# Group_05.net
KiCad netlist of a schematic drawn in EAGLE
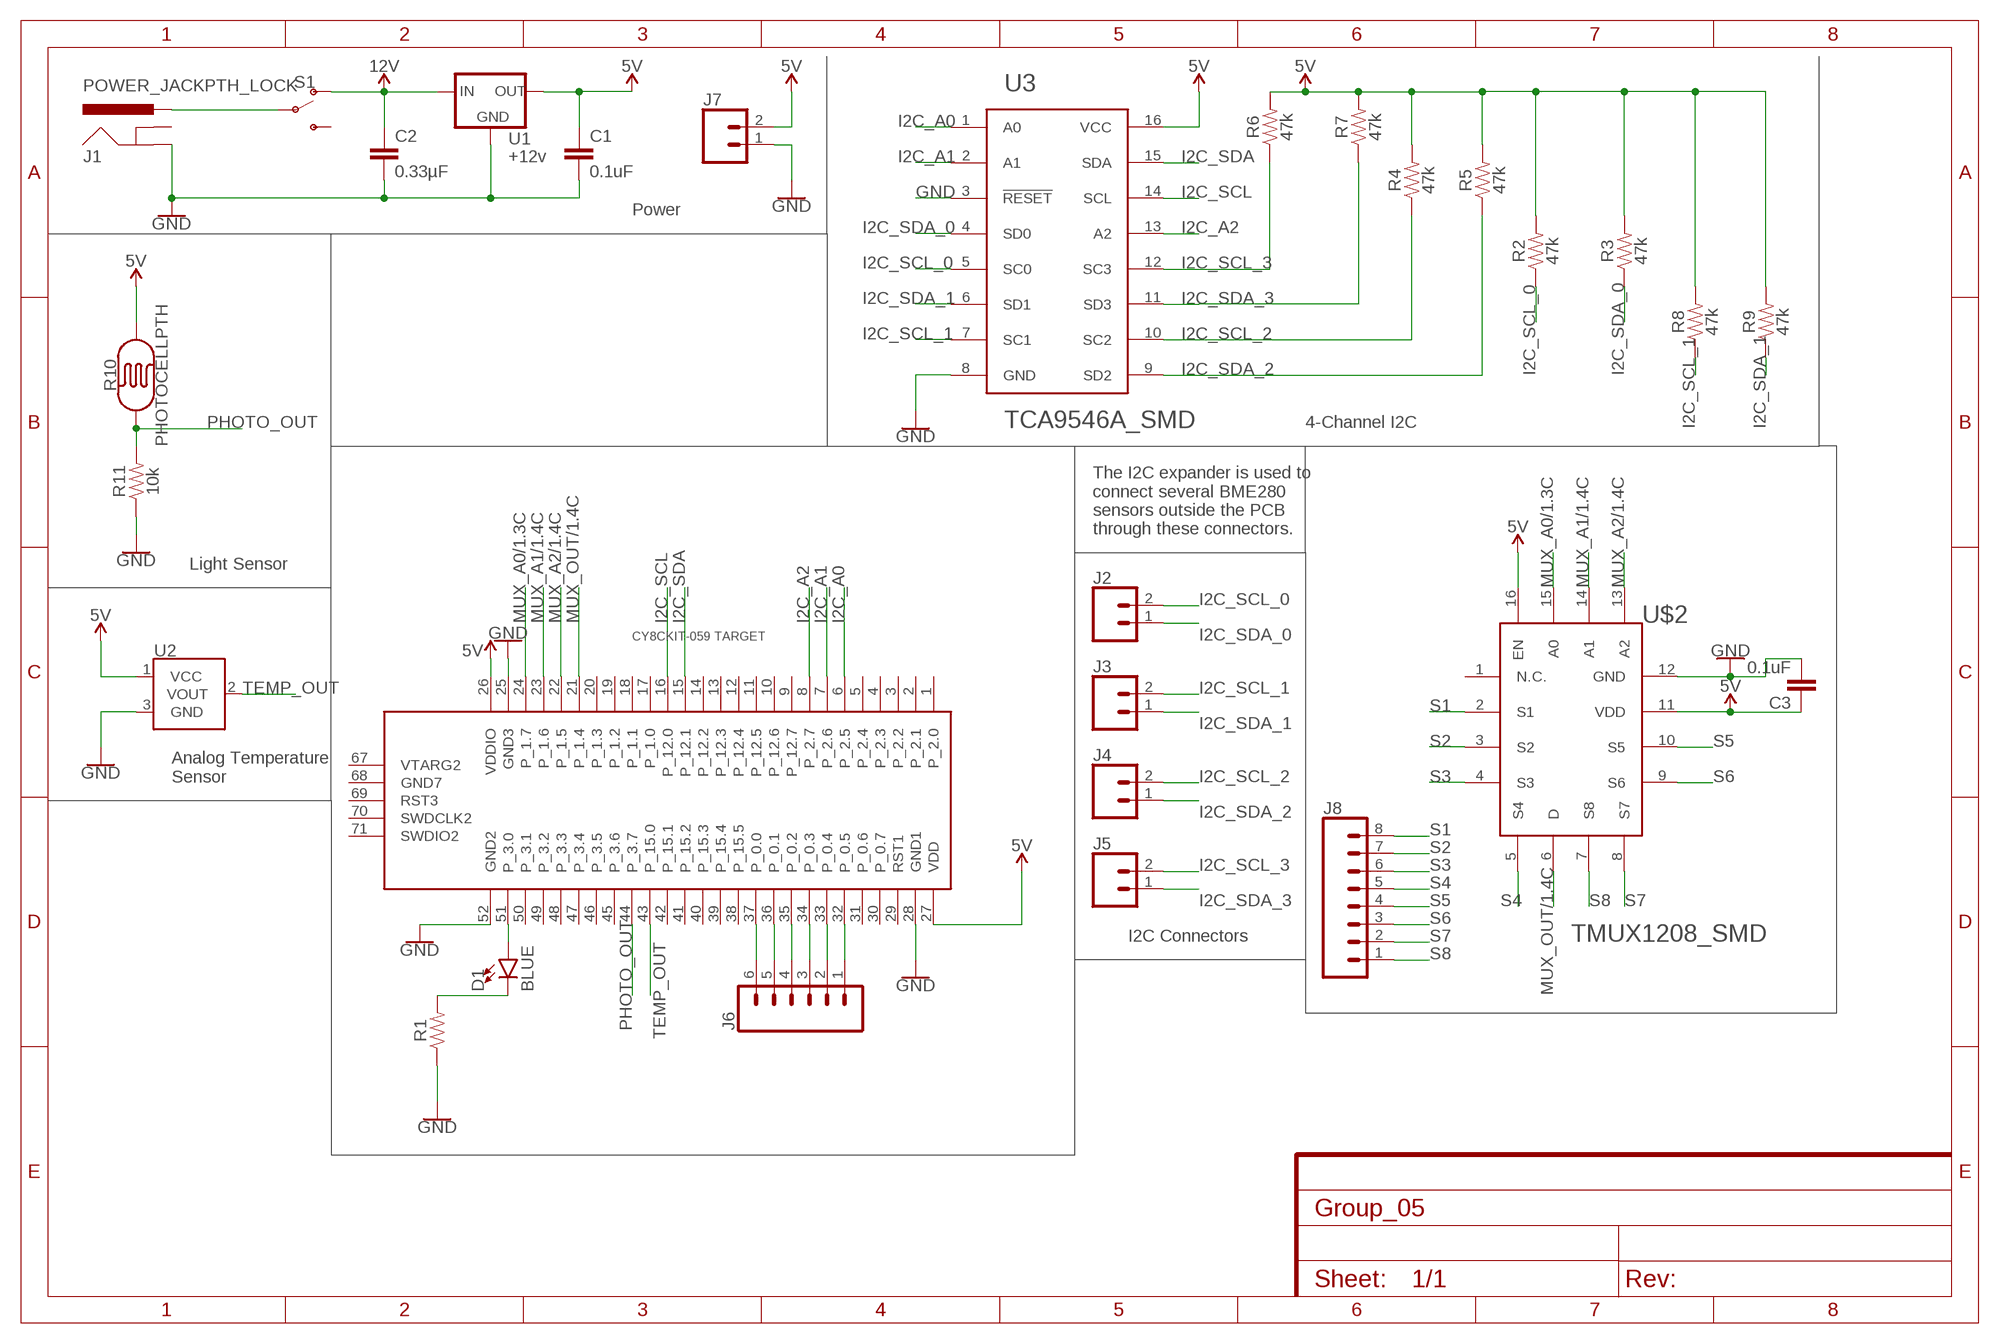
[diagram p0: schematic, sheet 1]

(export (version "E")
  (design (tool "Eeschema 10.0.6"))
  (components
    (comp (ref "C1")
      (value "0.1uF")
      (footprint "eagle-import:CAP-PTH-SMALL-KIT")
      (libsource (lib "eagle-import") (part "0.1UF-KIT-EZ-50V-20%"))
    )
    (comp (ref "C2")
      (value "0.33µF")
      (footprint "eagle-import:0805")
      (libsource (lib "eagle-import") (part "0.33UF/330NF-0805-50V-10%"))
    )
    (comp (ref "C3")
      (value "0.1uF")
      (footprint "eagle-import:CAP-PTH-SMALL-KIT")
      (libsource (lib "eagle-import") (part "0.1UF-KIT-EZ-50V-20%"))
    )
    (comp (ref "D1")
      (value "BLUE")
      (footprint "eagle-import:LED-1206")
      (libsource (lib "eagle-import") (part "LED-BLUE1206"))
    )
    (comp (ref "J1")
      (value "POWER_JACKPTH_LOCK")
      (footprint "eagle-import:POWER_JACK_PTH_LOCK")
      (libsource (lib "eagle-import") (part "POWER_JACKPTH_LOCK"))
    )
    (comp (ref "J2")
      (value "CONN_02")
      (footprint "eagle-import:1X02")
      (libsource (lib "eagle-import") (part "CONN_02"))
    )
    (comp (ref "J3")
      (value "CONN_02")
      (footprint "eagle-import:1X02")
      (libsource (lib "eagle-import") (part "CONN_02"))
    )
    (comp (ref "J4")
      (value "CONN_02")
      (footprint "eagle-import:1X02")
      (libsource (lib "eagle-import") (part "CONN_02"))
    )
    (comp (ref "J5")
      (value "CONN_02")
      (footprint "eagle-import:1X02")
      (libsource (lib "eagle-import") (part "CONN_02"))
    )
    (comp (ref "J6")
      (value "CONN_06LOCK")
      (footprint "eagle-import:1X06_LOCK")
      (libsource (lib "eagle-import") (part "CONN_06LOCK"))
    )
    (comp (ref "J7")
      (value "CONN_02")
      (footprint "eagle-import:1X02")
      (libsource (lib "eagle-import") (part "CONN_02"))
    )
    (comp (ref "J8")
      (value "CONN_08LOCK")
      (footprint "eagle-import:1X08_LOCK")
      (libsource (lib "eagle-import") (part "CONN_08LOCK"))
    )
    (comp (ref "R1")
      (value "RESISTORAXIAL-0.3")
      (footprint "eagle-import:AXIAL-0.3")
      (libsource (lib "eagle-import") (part "RESISTORAXIAL-0.3"))
    )
    (comp (ref "R2")
      (value "47k")
      (footprint "eagle-import:0603")
      (libsource (lib "eagle-import") (part "47KOHM-0603-1/10W-1%"))
    )
    (comp (ref "R3")
      (value "47k")
      (footprint "eagle-import:0603")
      (libsource (lib "eagle-import") (part "47KOHM-0603-1/10W-1%"))
    )
    (comp (ref "R4")
      (value "47k")
      (footprint "eagle-import:0603")
      (libsource (lib "eagle-import") (part "47KOHM-0603-1/10W-1%"))
    )
    (comp (ref "R5")
      (value "47k")
      (footprint "eagle-import:0603")
      (libsource (lib "eagle-import") (part "47KOHM-0603-1/10W-1%"))
    )
    (comp (ref "R6")
      (value "47k")
      (footprint "eagle-import:0603")
      (libsource (lib "eagle-import") (part "47KOHM-0603-1/10W-1%"))
    )
    (comp (ref "R7")
      (value "47k")
      (footprint "eagle-import:0603")
      (libsource (lib "eagle-import") (part "47KOHM-0603-1/10W-1%"))
    )
    (comp (ref "R8")
      (value "47k")
      (footprint "eagle-import:0603")
      (libsource (lib "eagle-import") (part "47KOHM-0603-1/10W-1%"))
    )
    (comp (ref "R9")
      (value "47k")
      (footprint "eagle-import:0603")
      (libsource (lib "eagle-import") (part "47KOHM-0603-1/10W-1%"))
    )
    (comp (ref "R10")
      (value "PHOTOCELLPTH")
      (footprint "eagle-import:PHOTOCELL")
      (libsource (lib "eagle-import") (part "PHOTOCELLPTH"))
    )
    (comp (ref "R11")
      (value "10k")
      (footprint "eagle-import:0603")
      (libsource (lib "eagle-import") (part "10KOHM-0603-1/10W-1%"))
    )
    (comp (ref "S1")
      (value "SWITCH-SPDT-PTH-11.6X4.0MM")
      (footprint "eagle-import:SWITCH_SPDT_PTH_11.6X4.0MM")
      (libsource (lib "eagle-import") (part "SWITCH-SPDT-PTH-11.6X4.0MM"))
    )
    (comp (ref "U$1")
      (value "CY8CKIT-059_TARGET")
      (footprint "eagle-import:CY8CKIT-059_TARGET")
      (libsource (lib "eagle-import") (part "CY8CKIT-059_TARGET"))
    )
    (comp (ref "U$2")
      (value "TMUX1208_SMD")
      (footprint "eagle-import:QFN16")
      (libsource (lib "eagle-import") (part "TMUX1208_SMD"))
    )
    (comp (ref "U1")
      (value "+12v")
      (footprint "eagle-import:TO-252")
      (libsource (lib "eagle-import") (part "V_REG_78XX7812"))
    )
    (comp (ref "U2")
      (value "TMP36GT9")
      (footprint "eagle-import:TO-92")
      (libsource (lib "eagle-import") (part "TMP36GT9"))
    )
    (comp (ref "U3")
      (value "TCA9546A_SMD")
      (footprint "eagle-import:TSSOP16")
      (libsource (lib "eagle-import") (part "TCA9546A_SMD"))
    )
  )
  (nets
    (net (code "1") (name "/I2C_A0") (class "Default")
      (node (ref "U$1") (pin "6") (pinfunction "P_2.5_6") (pintype "bidirectional"))
      (node (ref "U3") (pin "1") (pinfunction "A0_1") (pintype "bidirectional"))
    )
    (net (code "2") (name "/I2C_A1") (class "Default")
      (node (ref "U$1") (pin "7") (pinfunction "P_2.6_7") (pintype "bidirectional"))
      (node (ref "U3") (pin "2") (pinfunction "A1_2") (pintype "bidirectional"))
    )
    (net (code "3") (name "/I2C_A2") (class "Default")
      (node (ref "U$1") (pin "8") (pinfunction "P_2.7_8") (pintype "bidirectional"))
      (node (ref "U3") (pin "13") (pinfunction "A2_13") (pintype "bidirectional"))
    )
    (net (code "4") (name "/I2C_SCL") (class "Default")
      (node (ref "U$1") (pin "16") (pinfunction "P_12.0_16") (pintype "bidirectional"))
      (node (ref "U3") (pin "14") (pinfunction "SCL_14") (pintype "bidirectional"))
    )
    (net (code "5") (name "/I2C_SCL_0") (class "Default")
      (node (ref "J2") (pin "2") (pinfunction "2_2") (pintype "passive"))
      (node (ref "R2") (pin "1") (pinfunction "1_1") (pintype "passive"))
      (node (ref "U3") (pin "5") (pinfunction "SC0_5") (pintype "bidirectional"))
    )
    (net (code "6") (name "/I2C_SCL_1") (class "Default")
      (node (ref "J3") (pin "2") (pinfunction "2_2") (pintype "passive"))
      (node (ref "R8") (pin "1") (pinfunction "1_1") (pintype "passive"))
      (node (ref "U3") (pin "7") (pinfunction "SC1_7") (pintype "bidirectional"))
    )
    (net (code "7") (name "/I2C_SCL_2") (class "Default")
      (node (ref "J4") (pin "2") (pinfunction "2_2") (pintype "passive"))
      (node (ref "R4") (pin "1") (pinfunction "1_1") (pintype "passive"))
      (node (ref "U3") (pin "10") (pinfunction "SC2_10") (pintype "bidirectional"))
    )
    (net (code "8") (name "/I2C_SCL_3") (class "Default")
      (node (ref "J5") (pin "2") (pinfunction "2_2") (pintype "passive"))
      (node (ref "R6") (pin "1") (pinfunction "1_1") (pintype "passive"))
      (node (ref "U3") (pin "12") (pinfunction "SC3_12") (pintype "bidirectional"))
    )
    (net (code "9") (name "/I2C_SDA") (class "Default")
      (node (ref "U$1") (pin "15") (pinfunction "P_12.1_15") (pintype "bidirectional"))
      (node (ref "U3") (pin "15") (pinfunction "SDA_15") (pintype "bidirectional"))
    )
    (net (code "10") (name "/I2C_SDA_0") (class "Default")
      (node (ref "J2") (pin "1") (pinfunction "1_1") (pintype "passive"))
      (node (ref "R3") (pin "1") (pinfunction "1_1") (pintype "passive"))
      (node (ref "U3") (pin "4") (pinfunction "SD0_4") (pintype "bidirectional"))
    )
    (net (code "11") (name "/I2C_SDA_1") (class "Default")
      (node (ref "J3") (pin "1") (pinfunction "1_1") (pintype "passive"))
      (node (ref "R9") (pin "1") (pinfunction "1_1") (pintype "passive"))
      (node (ref "U3") (pin "6") (pinfunction "SD1_6") (pintype "bidirectional"))
    )
    (net (code "12") (name "/I2C_SDA_2") (class "Default")
      (node (ref "J4") (pin "1") (pinfunction "1_1") (pintype "passive"))
      (node (ref "R5") (pin "1") (pinfunction "1_1") (pintype "passive"))
      (node (ref "U3") (pin "9") (pinfunction "SD2_9") (pintype "bidirectional"))
    )
    (net (code "13") (name "/I2C_SDA_3") (class "Default")
      (node (ref "J5") (pin "1") (pinfunction "1_1") (pintype "passive"))
      (node (ref "R7") (pin "1") (pinfunction "1_1") (pintype "passive"))
      (node (ref "U3") (pin "11") (pinfunction "SD3_11") (pintype "bidirectional"))
    )
    (net (code "14") (name "/MUX_A0{slash}1.3C") (class "Default")
      (node (ref "U$1") (pin "24") (pinfunction "P_1.7_24") (pintype "bidirectional"))
      (node (ref "U$2") (pin "15") (pinfunction "A0_15") (pintype "bidirectional"))
    )
    (net (code "15") (name "/MUX_A1{slash}1.4C") (class "Default")
      (node (ref "U$1") (pin "23") (pinfunction "P_1.6_23") (pintype "bidirectional"))
      (node (ref "U$2") (pin "14") (pinfunction "A1_14") (pintype "bidirectional"))
    )
    (net (code "16") (name "/MUX_A2{slash}1.4C") (class "Default")
      (node (ref "U$1") (pin "22") (pinfunction "P_1.5_22") (pintype "bidirectional"))
      (node (ref "U$2") (pin "13") (pinfunction "A2_13") (pintype "bidirectional"))
    )
    (net (code "17") (name "/MUX_OUT{slash}1.4C") (class "Default")
      (node (ref "U$1") (pin "21") (pinfunction "P_1.4_21") (pintype "bidirectional"))
      (node (ref "U$2") (pin "6") (pinfunction "D_6") (pintype "bidirectional"))
    )
    (net (code "18") (name "/PHOTO_OUT") (class "Default")
      (node (ref "R10") (pin "1") (pinfunction "P$1_1") (pintype "bidirectional"))
      (node (ref "R11") (pin "2") (pinfunction "2_2") (pintype "passive"))
      (node (ref "U$1") (pin "44") (pinfunction "P_3.7_44") (pintype "bidirectional"))
    )
    (net (code "19") (name "/S1") (class "Default")
      (node (ref "J8") (pin "8") (pinfunction "8_8") (pintype "passive"))
      (node (ref "U$2") (pin "2") (pinfunction "S1_2") (pintype "bidirectional"))
    )
    (net (code "20") (name "/S2") (class "Default")
      (node (ref "J8") (pin "7") (pinfunction "7_7") (pintype "passive"))
      (node (ref "U$2") (pin "3") (pinfunction "S2_3") (pintype "bidirectional"))
    )
    (net (code "21") (name "/S3") (class "Default")
      (node (ref "J8") (pin "6") (pinfunction "6_6") (pintype "passive"))
      (node (ref "U$2") (pin "4") (pinfunction "S3_4") (pintype "bidirectional"))
    )
    (net (code "22") (name "/S4") (class "Default")
      (node (ref "J8") (pin "5") (pinfunction "5_5") (pintype "passive"))
      (node (ref "U$2") (pin "5") (pinfunction "S4_5") (pintype "bidirectional"))
    )
    (net (code "23") (name "/S5") (class "Default")
      (node (ref "J8") (pin "4") (pinfunction "4_4") (pintype "passive"))
      (node (ref "U$2") (pin "10") (pinfunction "S5_10") (pintype "bidirectional"))
    )
    (net (code "24") (name "/S6") (class "Default")
      (node (ref "J8") (pin "3") (pinfunction "3_3") (pintype "passive"))
      (node (ref "U$2") (pin "9") (pinfunction "S6_9") (pintype "bidirectional"))
    )
    (net (code "25") (name "/S7") (class "Default")
      (node (ref "J8") (pin "2") (pinfunction "2_2") (pintype "passive"))
      (node (ref "U$2") (pin "8") (pinfunction "S7_8") (pintype "bidirectional"))
    )
    (net (code "26") (name "/S8") (class "Default")
      (node (ref "J8") (pin "1") (pinfunction "1_1") (pintype "passive"))
      (node (ref "U$2") (pin "7") (pinfunction "S8_7") (pintype "bidirectional"))
    )
    (net (code "27") (name "/TEMP_OUT") (class "Default")
      (node (ref "U$1") (pin "43") (pinfunction "P_15.0_43") (pintype "bidirectional"))
      (node (ref "U2") (pin "2") (pinfunction "VOUT_2") (pintype "bidirectional"))
    )
    (net (code "28") (name "5V") (class "Default")
      (node (ref "C1") (pin "1") (pinfunction "1_1") (pintype "passive"))
      (node (ref "C3") (pin "1") (pinfunction "1_1") (pintype "passive"))
      (node (ref "J7") (pin "2") (pinfunction "2_2") (pintype "passive"))
      (node (ref "R10") (pin "2") (pinfunction "P$2_2") (pintype "bidirectional"))
      (node (ref "R2") (pin "2") (pinfunction "2_2") (pintype "passive"))
      (node (ref "R3") (pin "2") (pinfunction "2_2") (pintype "passive"))
      (node (ref "R4") (pin "2") (pinfunction "2_2") (pintype "passive"))
      (node (ref "R5") (pin "2") (pinfunction "2_2") (pintype "passive"))
      (node (ref "R6") (pin "2") (pinfunction "2_2") (pintype "passive"))
      (node (ref "R7") (pin "2") (pinfunction "2_2") (pintype "passive"))
      (node (ref "R8") (pin "2") (pinfunction "2_2") (pintype "passive"))
      (node (ref "R9") (pin "2") (pinfunction "2_2") (pintype "passive"))
      (node (ref "U$1") (pin "26") (pinfunction "VDDIO_26") (pintype "bidirectional"))
      (node (ref "U$1") (pin "27") (pinfunction "VDD_27") (pintype "bidirectional"))
      (node (ref "U$2") (pin "11") (pinfunction "VDD_11") (pintype "bidirectional"))
      (node (ref "U$2") (pin "16") (pinfunction "EN_16") (pintype "bidirectional"))
      (node (ref "U1") (pin "2") (pinfunction "OUT_2") (pintype "passive"))
      (node (ref "U2") (pin "1") (pinfunction "VCC_1") (pintype "bidirectional"))
      (node (ref "U3") (pin "16") (pinfunction "VCC_16") (pintype "bidirectional"))
    )
    (net (code "29") (name "12V") (class "Default")
      (node (ref "C2") (pin "1") (pinfunction "1_1") (pintype "passive"))
      (node (ref "S1") (pin "1") (pinfunction "O_1") (pintype "passive"))
      (node (ref "U1") (pin "1") (pinfunction "IN_1") (pintype "input"))
    )
    (net (code "30") (name "GND") (class "Default")
      (node (ref "C1") (pin "2") (pinfunction "2_2") (pintype "passive"))
      (node (ref "C2") (pin "2") (pinfunction "2_2") (pintype "passive"))
      (node (ref "C3") (pin "2") (pinfunction "2_2") (pintype "passive"))
      (node (ref "J1") (pin "GND") (pinfunction "GND_GND") (pintype "bidirectional"))
      (node (ref "J7") (pin "1") (pinfunction "1_1") (pintype "passive"))
      (node (ref "R1") (pin "P$1") (pinfunction "1_P$1") (pintype "passive"))
      (node (ref "R11") (pin "1") (pinfunction "1_1") (pintype "passive"))
      (node (ref "U$1") (pin "25") (pinfunction "GND3_25") (pintype "bidirectional"))
      (node (ref "U$1") (pin "28") (pinfunction "GND1_28") (pintype "bidirectional"))
      (node (ref "U$1") (pin "52") (pinfunction "GND2_52") (pintype "bidirectional"))
      (node (ref "U$2") (pin "12") (pinfunction "GND_12") (pintype "bidirectional"))
      (node (ref "U1") (pin "3") (pinfunction "GND_3") (pintype "input"))
      (node (ref "U2") (pin "3") (pinfunction "GND_3") (pintype "bidirectional"))
      (node (ref "U3") (pin "3") (pinfunction "~{RESET}_3") (pintype "bidirectional"))
      (node (ref "U3") (pin "8") (pinfunction "GND_8") (pintype "bidirectional"))
    )
    (net (code "31") (name "Net-(R1-2)") (class "Default")
      (node (ref "D1") (pin "C") (pinfunction "C_C") (pintype "passive"))
      (node (ref "R1") (pin "P$2") (pinfunction "2_P$2") (pintype "passive"))
    )
    (net (code "32") (name "Net-(S1-P)") (class "Default")
      (node (ref "J1") (pin "PWR") (pinfunction "PWR_PWR") (pintype "bidirectional"))
      (node (ref "S1") (pin "2") (pinfunction "P_2") (pintype "passive"))
    )
    (net (code "33") (name "Net-(U$1-P_0.0)") (class "Default")
      (node (ref "J6") (pin "6") (pinfunction "6_6") (pintype "passive"))
      (node (ref "U$1") (pin "37") (pinfunction "P_0.0_37") (pintype "bidirectional"))
    )
    (net (code "34") (name "Net-(U$1-P_0.1)") (class "Default")
      (node (ref "J6") (pin "5") (pinfunction "5_5") (pintype "passive"))
      (node (ref "U$1") (pin "36") (pinfunction "P_0.1_36") (pintype "bidirectional"))
    )
    (net (code "35") (name "Net-(U$1-P_0.2)") (class "Default")
      (node (ref "J6") (pin "4") (pinfunction "4_4") (pintype "passive"))
      (node (ref "U$1") (pin "35") (pinfunction "P_0.2_35") (pintype "bidirectional"))
    )
    (net (code "36") (name "Net-(U$1-P_0.3)") (class "Default")
      (node (ref "J6") (pin "3") (pinfunction "3_3") (pintype "passive"))
      (node (ref "U$1") (pin "34") (pinfunction "P_0.3_34") (pintype "bidirectional"))
    )
    (net (code "37") (name "Net-(U$1-P_0.4)") (class "Default")
      (node (ref "J6") (pin "2") (pinfunction "2_2") (pintype "passive"))
      (node (ref "U$1") (pin "33") (pinfunction "P_0.4_33") (pintype "bidirectional"))
    )
    (net (code "38") (name "Net-(U$1-P_0.5)") (class "Default")
      (node (ref "J6") (pin "1") (pinfunction "1_1") (pintype "passive"))
      (node (ref "U$1") (pin "32") (pinfunction "P_0.5_32") (pintype "bidirectional"))
    )
    (net (code "39") (name "Net-(U$1-P_3.0)") (class "Default")
      (node (ref "D1") (pin "A") (pinfunction "A_A") (pintype "passive"))
      (node (ref "U$1") (pin "51") (pinfunction "P_3.0_51") (pintype "bidirectional"))
    )
    (net (code "40") (name "unconnected-(J1-PadGNDBREAK)") (class "Default")
      (node (ref "J1") (pin "GNDBREAK") (pinfunction "GNDBREAK_GNDBREAK") (pintype "bidirectional"))
    )
    (net (code "41") (name "unconnected-(S1-S-Pad3)") (class "Default")
      (node (ref "S1") (pin "3") (pinfunction "S_3") (pintype "passive"))
    )
    (net (code "42") (name "unconnected-(U$1-GND7-Pad68)") (class "Default")
      (node (ref "U$1") (pin "68") (pinfunction "GND7_68") (pintype "bidirectional"))
    )
    (net (code "43") (name "unconnected-(U$1-P_0.6-Pad31)") (class "Default")
      (node (ref "U$1") (pin "31") (pinfunction "P_0.6_31") (pintype "bidirectional"))
    )
    (net (code "44") (name "unconnected-(U$1-P_0.7-Pad30)") (class "Default")
      (node (ref "U$1") (pin "30") (pinfunction "P_0.7_30") (pintype "bidirectional"))
    )
    (net (code "45") (name "unconnected-(U$1-P_1.0-Pad17)") (class "Default")
      (node (ref "U$1") (pin "17") (pinfunction "P_1.0_17") (pintype "bidirectional"))
    )
    (net (code "46") (name "unconnected-(U$1-P_1.1-Pad18)") (class "Default")
      (node (ref "U$1") (pin "18") (pinfunction "P_1.1_18") (pintype "bidirectional"))
    )
    (net (code "47") (name "unconnected-(U$1-P_1.2-Pad19)") (class "Default")
      (node (ref "U$1") (pin "19") (pinfunction "P_1.2_19") (pintype "bidirectional"))
    )
    (net (code "48") (name "unconnected-(U$1-P_1.3-Pad20)") (class "Default")
      (node (ref "U$1") (pin "20") (pinfunction "P_1.3_20") (pintype "bidirectional"))
    )
    (net (code "49") (name "unconnected-(U$1-P_2.0-Pad1)") (class "Default")
      (node (ref "U$1") (pin "1") (pinfunction "P_2.0_1") (pintype "bidirectional"))
    )
    (net (code "50") (name "unconnected-(U$1-P_2.1-Pad2)") (class "Default")
      (node (ref "U$1") (pin "2") (pinfunction "P_2.1_2") (pintype "bidirectional"))
    )
    (net (code "51") (name "unconnected-(U$1-P_2.2-Pad3)") (class "Default")
      (node (ref "U$1") (pin "3") (pinfunction "P_2.2_3") (pintype "bidirectional"))
    )
    (net (code "52") (name "unconnected-(U$1-P_2.3-Pad4)") (class "Default")
      (node (ref "U$1") (pin "4") (pinfunction "P_2.3_4") (pintype "bidirectional"))
    )
    (net (code "53") (name "unconnected-(U$1-P_2.4-Pad5)") (class "Default")
      (node (ref "U$1") (pin "5") (pinfunction "P_2.4_5") (pintype "bidirectional"))
    )
    (net (code "54") (name "unconnected-(U$1-P_3.1-Pad50)") (class "Default")
      (node (ref "U$1") (pin "50") (pinfunction "P_3.1_50") (pintype "bidirectional"))
    )
    (net (code "55") (name "unconnected-(U$1-P_3.2-Pad49)") (class "Default")
      (node (ref "U$1") (pin "49") (pinfunction "P_3.2_49") (pintype "bidirectional"))
    )
    (net (code "56") (name "unconnected-(U$1-P_3.3-Pad48)") (class "Default")
      (node (ref "U$1") (pin "48") (pinfunction "P_3.3_48") (pintype "bidirectional"))
    )
    (net (code "57") (name "unconnected-(U$1-P_3.4-Pad47)") (class "Default")
      (node (ref "U$1") (pin "47") (pinfunction "P_3.4_47") (pintype "bidirectional"))
    )
    (net (code "58") (name "unconnected-(U$1-P_3.5-Pad46)") (class "Default")
      (node (ref "U$1") (pin "46") (pinfunction "P_3.5_46") (pintype "bidirectional"))
    )
    (net (code "59") (name "unconnected-(U$1-P_3.6-Pad45)") (class "Default")
      (node (ref "U$1") (pin "45") (pinfunction "P_3.6_45") (pintype "bidirectional"))
    )
    (net (code "60") (name "unconnected-(U$1-P_12.2-Pad14)") (class "Default")
      (node (ref "U$1") (pin "14") (pinfunction "P_12.2_14") (pintype "bidirectional"))
    )
    (net (code "61") (name "unconnected-(U$1-P_12.3-Pad13)") (class "Default")
      (node (ref "U$1") (pin "13") (pinfunction "P_12.3_13") (pintype "bidirectional"))
    )
    (net (code "62") (name "unconnected-(U$1-P_12.4-Pad12)") (class "Default")
      (node (ref "U$1") (pin "12") (pinfunction "P_12.4_12") (pintype "bidirectional"))
    )
    (net (code "63") (name "unconnected-(U$1-P_12.5-Pad11)") (class "Default")
      (node (ref "U$1") (pin "11") (pinfunction "P_12.5_11") (pintype "bidirectional"))
    )
    (net (code "64") (name "unconnected-(U$1-P_12.6-Pad10)") (class "Default")
      (node (ref "U$1") (pin "10") (pinfunction "P_12.6_10") (pintype "bidirectional"))
    )
    (net (code "65") (name "unconnected-(U$1-P_12.7-Pad9)") (class "Default")
      (node (ref "U$1") (pin "9") (pinfunction "P_12.7_9") (pintype "bidirectional"))
    )
    (net (code "66") (name "unconnected-(U$1-P_15.1-Pad42)") (class "Default")
      (node (ref "U$1") (pin "42") (pinfunction "P_15.1_42") (pintype "bidirectional"))
    )
    (net (code "67") (name "unconnected-(U$1-P_15.2-Pad41)") (class "Default")
      (node (ref "U$1") (pin "41") (pinfunction "P_15.2_41") (pintype "bidirectional"))
    )
    (net (code "68") (name "unconnected-(U$1-P_15.3-Pad40)") (class "Default")
      (node (ref "U$1") (pin "40") (pinfunction "P_15.3_40") (pintype "bidirectional"))
    )
    (net (code "69") (name "unconnected-(U$1-P_15.4-Pad39)") (class "Default")
      (node (ref "U$1") (pin "39") (pinfunction "P_15.4_39") (pintype "bidirectional"))
    )
    (net (code "70") (name "unconnected-(U$1-P_15.5-Pad38)") (class "Default")
      (node (ref "U$1") (pin "38") (pinfunction "P_15.5_38") (pintype "bidirectional"))
    )
    (net (code "71") (name "unconnected-(U$1-RST1-Pad29)") (class "Default")
      (node (ref "U$1") (pin "29") (pinfunction "RST1_29") (pintype "bidirectional"))
    )
    (net (code "72") (name "unconnected-(U$1-RST3-Pad69)") (class "Default")
      (node (ref "U$1") (pin "69") (pinfunction "RST3_69") (pintype "bidirectional"))
    )
    (net (code "73") (name "unconnected-(U$1-SWDCLK2-Pad70)") (class "Default")
      (node (ref "U$1") (pin "70") (pinfunction "SWDCLK2_70") (pintype "bidirectional"))
    )
    (net (code "74") (name "unconnected-(U$1-SWDIO2-Pad71)") (class "Default")
      (node (ref "U$1") (pin "71") (pinfunction "SWDIO2_71") (pintype "bidirectional"))
    )
    (net (code "75") (name "unconnected-(U$1-VTARG2-Pad67)") (class "Default")
      (node (ref "U$1") (pin "67") (pinfunction "VTARG2_67") (pintype "bidirectional"))
    )
    (net (code "76") (name "unconnected-(U$2-N.C.-Pad1)") (class "Default")
      (node (ref "U$2") (pin "1") (pinfunction "N.C._1") (pintype "bidirectional"))
    )
  )
)
